# 27-AudioEncode.net
KiCad netlist of a schematic drawn in Altium Designer
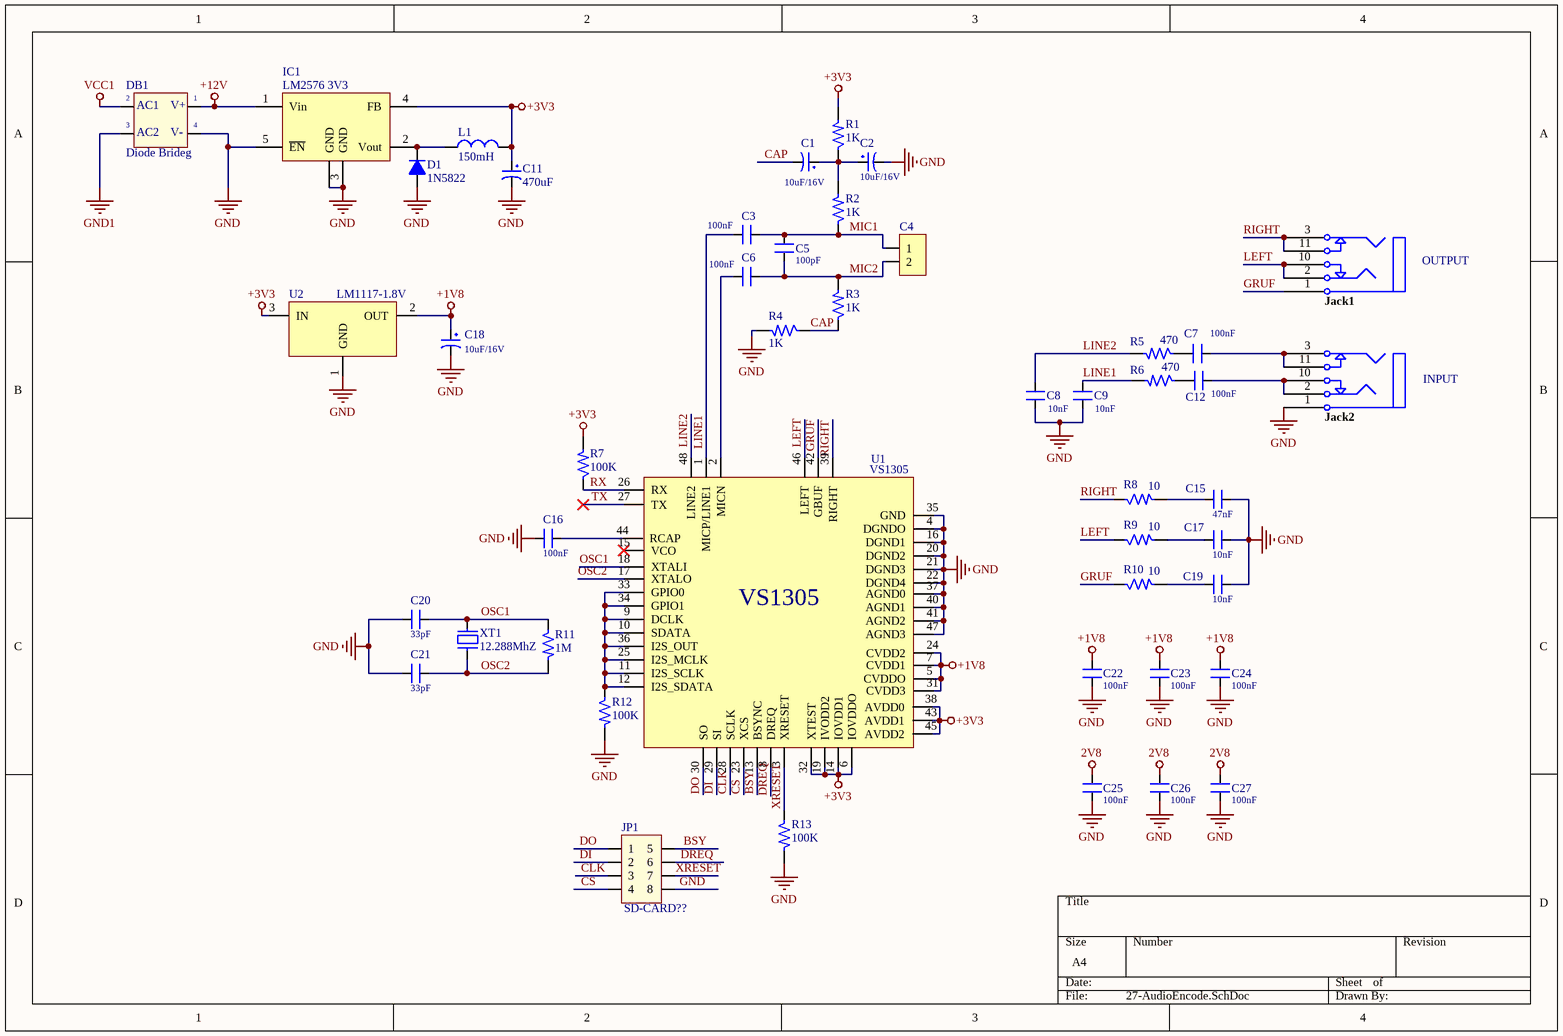
[diagram p0: 27-AudioEncode.SchDoc]

(export (version "E")
  (design (tool "Eeschema 10.0.6"))
  (components
    (comp (ref "C1") (value "10uF/16V") (footprint "C-TANT-7343") (libsource (lib "") (part "Capacitor_1")))
    (comp (ref "C2") (value "10uF/16V") (footprint "C-TANT-7343") (libsource (lib "") (part "Capacitor_1")))
    (comp (ref "C3") (value "100nF") (footprint "CER-0805") (libsource (lib "MrQuan") (part "Ceramic")))
    (comp (ref "C4")
      (value "JP2")
      (footprint "JP2-C1T")
      (description "WR-PHD 2.54 mm Angled Socket Header")
      (fields
        (field (name "MANUFACTURER") "Würth Elektronik eiSos GmbH")
        (field (name "PARTNO") "613002143121")
        (field (name "CREATED BY") "Karrer Zheng")
      )
      (libsource (lib "LIBRARY") (part "JP2"))
    )
    (comp (ref "C5") (value "100pF") (footprint "CER-0805") (libsource (lib "MrQuan") (part "Ceramic")))
    (comp (ref "C6") (value "100nF") (footprint "CER-0805") (libsource (lib "MrQuan") (part "Ceramic")))
    (comp (ref "C7") (value "100nF") (footprint "CER-0805") (libsource (lib "MrQuan") (part "Ceramic")))
    (comp (ref "C8") (value "10nF") (footprint "CER-0805") (libsource (lib "MrQuan") (part "Ceramic")))
    (comp (ref "C9") (value "10nF") (footprint "CER-0805") (libsource (lib "MrQuan") (part "Ceramic")))
    (comp (ref "C11")
      (value "470uF")
      (footprint "C-ALU-D6.5")
      (description "Cap P  0,1uF < 22uF , 16 - 50V")
      (libsource (lib "PART") (part "CP1"))
    )
    (comp (ref "C12") (value "100nF") (footprint "CER-0805") (libsource (lib "MrQuan") (part "Ceramic")))
    (comp (ref "C15") (value "47nF") (footprint "CER-0805") (libsource (lib "MrQuan") (part "Ceramic")))
    (comp (ref "C16") (value "100nF") (footprint "CER-0805") (libsource (lib "MrQuan") (part "Ceramic")))
    (comp (ref "C17") (value "10nF") (footprint "CER-0805") (libsource (lib "MrQuan") (part "Ceramic")))
    (comp (ref "C18")
      (value "10uF/16V")
      (footprint "C-TANT-7343")
      (libsource (lib "MrQuan") (part "Capacitor"))
    )
    (comp (ref "C19") (value "10nF") (footprint "CER-0805") (libsource (lib "MrQuan") (part "Ceramic")))
    (comp (ref "C20") (value "33pF") (footprint "CER-0805") (libsource (lib "MrQuan") (part "Ceramic")))
    (comp (ref "C21") (value "33pF") (footprint "CER-0805") (libsource (lib "MrQuan") (part "Ceramic")))
    (comp (ref "C22") (value "100nF") (footprint "C-0805") (libsource (lib "MrQuan") (part "Ceramic")))
    (comp (ref "C23") (value "100nF") (footprint "C-0805") (libsource (lib "MrQuan") (part "Ceramic")))
    (comp (ref "C24") (value "100nF") (footprint "C-0805") (libsource (lib "MrQuan") (part "Ceramic")))
    (comp (ref "C25") (value "100nF") (footprint "C-0805") (libsource (lib "MrQuan") (part "Ceramic")))
    (comp (ref "C26") (value "100nF") (footprint "C-0805") (libsource (lib "MrQuan") (part "Ceramic")))
    (comp (ref "C27") (value "100nF") (footprint "C-0805") (libsource (lib "MrQuan") (part "Ceramic")))
    (comp (ref "D1")
      (value "1N5822")
      (footprint "D-DO214-AB")
      (description "Diode 1A")
      (libsource (lib "PART") (part "D1A"))
    )
    (comp (ref "DB1")
      (value "Diode Brideg")
      (footprint "D-DB-1A-SMD")
      (description "Convert AC to DC voltage, 4 pin")
      (libsource (lib "PART") (part "DB"))
    )
    (comp (ref "IC1")
      (value "LM2576 3V3")
      (footprint "TO-263-5L")
      (description "LM2576")
      (libsource (lib "PART") (part "LM2576"))
    )
    (comp (ref "Jack1")
      (value "AUDIO MIC BLACK HEADER")
      (footprint "CON MIC1")
      (libsource (lib "LIBRARY") (part "CON MIC1"))
    )
    (comp (ref "Jack2")
      (value "AUDIO MIC BLACK HEADER")
      (footprint "CON MIC1")
      (libsource (lib "LIBRARY") (part "CON MIC1"))
    )
    (comp (ref "JP1")
      (value "SD-CARD??")
      (footprint "JP4x2")
      (description "Connector 4x2")
      (libsource (lib "syhaunguyen") (part "JP4x2"))
    )
    (comp (ref "L1")
      (value "150mH")
      (footprint "L-SMD-10x10")
      (description "Inductor")
      (libsource (lib "PART") (part "L1"))
    )
    (comp (ref "R1") (value "1K") (footprint "RES-0805") (libsource (lib "MrQuan") (part "Res1/4W")))
    (comp (ref "R2") (value "1K") (footprint "RES-0805") (libsource (lib "MrQuan") (part "Res1/4W")))
    (comp (ref "R3") (value "1K") (footprint "RES-0805") (libsource (lib "MrQuan") (part "Res1/4W")))
    (comp (ref "R4") (value "1K") (footprint "RES-0805") (libsource (lib "MrQuan") (part "Res1/4W")))
    (comp (ref "R5") (value "470") (footprint "RES-0805") (libsource (lib "MrQuan") (part "Res1/4W")))
    (comp (ref "R6") (value "470") (footprint "RES-0805") (libsource (lib "MrQuan") (part "Res1/4W")))
    (comp (ref "R7") (value "100K") (footprint "RES-0805") (libsource (lib "MrQuan") (part "Res1/4W")))
    (comp (ref "R8") (value "10") (footprint "RES-0805") (libsource (lib "MrQuan") (part "Res1/4W")))
    (comp (ref "R9") (value "10") (footprint "RES-0805") (libsource (lib "MrQuan") (part "Res1/4W")))
    (comp (ref "R10") (value "10") (footprint "RES-0805") (libsource (lib "MrQuan") (part "Res1/4W")))
    (comp (ref "R11") (value "1M") (footprint "RES-0805") (libsource (lib "MrQuan") (part "Res1/4W")))
    (comp (ref "R12") (value "100K") (footprint "RES-0805") (libsource (lib "MrQuan") (part "Res1/4W")))
    (comp (ref "R13") (value "100K") (footprint "RES-0805") (libsource (lib "MrQuan") (part "Res1/4W")))
    (comp (ref "U1") (value "VS1305") (footprint "QFP_48") (libsource (lib "MrQuan") (part "VS1305")))
    (comp (ref "U2")
      (value "LM1117-1.8V")
      (footprint "SOT223")
      (description "800mA Low-Dropout Linear Regulator")
      (fields (field (name "CREATOR") "Nguyen Ba Bien"))
      (libsource (lib "LIBRARY") (part "LM1117"))
    )
    (comp (ref "XT1") (value "12.288MhZ") (footprint "XT SMD5032") (libsource (lib "MrQuan") (part "XT")))
  )
  (nets
    (net (code "1") (name "+1V8") (class "Default")
      (node (ref "C18") (pin "1") (pinfunction "1_1") (pintype "passive"))
      (node (ref "C22") (pin "2") (pinfunction "2_2") (pintype "passive"))
      (node (ref "C23") (pin "2") (pinfunction "2_2") (pintype "passive"))
      (node (ref "C24") (pin "2") (pinfunction "2_2") (pintype "passive"))
      (node (ref "U2") (pin "2") (pinfunction "OUT_2") (pintype "passive"))
    )
    (net (code "2") (name "+3V3") (class "Default")
      (node (ref "C11") (pin "1") (pinfunction "1_1") (pintype "passive"))
      (node (ref "IC1") (pin "4") (pinfunction "FB_4") (pintype "passive"))
      (node (ref "L1") (pin "2") (pinfunction "2_2") (pintype "passive"))
      (node (ref "R1") (pin "2") (pinfunction "2_2") (pintype "passive"))
      (node (ref "R7") (pin "2") (pinfunction "2_2") (pintype "passive"))
      (node (ref "U1") (pin "14") (pinfunction "IOVDD1_14") (pintype "passive"))
      (node (ref "U1") (pin "19") (pinfunction "IVODD2_19") (pintype "passive"))
      (node (ref "U1") (pin "32") (pinfunction "XTEST_32") (pintype "passive"))
      (node (ref "U1") (pin "6") (pinfunction "IOVDDO_6") (pintype "passive"))
      (node (ref "U2") (pin "3") (pinfunction "IN_3") (pintype "passive"))
    )
    (net (code "3") (name "+12V") (class "Default")
      (node (ref "DB1") (pin "3") (pinfunction "AC2_3") (pintype "passive"))
      (node (ref "IC1") (pin "1") (pinfunction "Vin_1") (pintype "passive"))
    )
    (net (code "4") (name "/BSY") (class "Default")
      (node (ref "JP1") (pin "5") (pinfunction "5_5") (pintype "passive"))
      (node (ref "U1") (pin "13") (pinfunction "BSYNC_13") (pintype "passive"))
    )
    (net (code "5") (name "/CAP") (class "Default")
      (node (ref "C1") (pin "2") (pinfunction "2_2") (pintype "passive"))
      (node (ref "R3") (pin "1") (pinfunction "1_1") (pintype "passive"))
      (node (ref "R4") (pin "1") (pinfunction "1_1") (pintype "passive"))
    )
    (net (code "6") (name "/CLK") (class "Default")
      (node (ref "JP1") (pin "3") (pinfunction "3_3") (pintype "passive"))
      (node (ref "U1") (pin "28") (pinfunction "SCLK_28") (pintype "passive"))
    )
    (net (code "7") (name "/CS") (class "Default")
      (node (ref "JP1") (pin "4") (pinfunction "4_4") (pintype "passive"))
      (node (ref "U1") (pin "23") (pinfunction "XCS_23") (pintype "passive"))
    )
    (net (code "8") (name "/DI") (class "Default")
      (node (ref "JP1") (pin "2") (pinfunction "2_2") (pintype "passive"))
      (node (ref "U1") (pin "29") (pinfunction "SI_29") (pintype "passive"))
    )
    (net (code "9") (name "/DO") (class "Default")
      (node (ref "JP1") (pin "1") (pinfunction "1_1") (pintype "passive"))
      (node (ref "U1") (pin "30") (pinfunction "SO_30") (pintype "passive"))
    )
    (net (code "10") (name "/DREQ") (class "Default")
      (node (ref "JP1") (pin "6") (pinfunction "6_6") (pintype "passive"))
      (node (ref "U1") (pin "8") (pinfunction "DREQ_8") (pintype "passive"))
    )
    (net (code "11") (name "/GRUF") (class "Default")
      (node (ref "Jack1") (pin "1") (pintype "passive"))
      (node (ref "R10") (pin "1") (pinfunction "1_1") (pintype "passive"))
      (node (ref "U1") (pin "42") (pinfunction "GBUF_42") (pintype "passive"))
    )
    (net (code "12") (name "/LEFT") (class "Default")
      (node (ref "Jack1") (pin "10") (pintype "passive"))
      (node (ref "Jack1") (pin "2") (pintype "passive"))
      (node (ref "R9") (pin "1") (pinfunction "1_1") (pintype "passive"))
      (node (ref "U1") (pin "46") (pinfunction "LEFT_46") (pintype "passive"))
    )
    (net (code "13") (name "/LINE1") (class "Default")
      (node (ref "C3") (pin "2") (pinfunction "2_2") (pintype "passive"))
      (node (ref "C9") (pin "2") (pinfunction "2_2") (pintype "passive"))
      (node (ref "R6") (pin "2") (pinfunction "2_2") (pintype "passive"))
      (node (ref "U1") (pin "1") (pinfunction "MICP/LINE1_1") (pintype "passive"))
    )
    (net (code "14") (name "/LINE2") (class "Default")
      (node (ref "C8") (pin "2") (pinfunction "2_2") (pintype "passive"))
      (node (ref "R5") (pin "2") (pinfunction "2_2") (pintype "passive"))
      (node (ref "U1") (pin "48") (pinfunction "LINE2_48") (pintype "passive"))
    )
    (net (code "15") (name "/MIC1") (class "Default")
      (node (ref "C3") (pin "1") (pinfunction "1_1") (pintype "passive"))
      (node (ref "C4") (pin "1") (pinfunction "1_1") (pintype "passive"))
      (node (ref "C5") (pin "1") (pinfunction "1_1") (pintype "passive"))
      (node (ref "R2") (pin "1") (pinfunction "1_1") (pintype "passive"))
    )
    (net (code "16") (name "/MIC2") (class "Default")
      (node (ref "C4") (pin "2") (pinfunction "2_2") (pintype "passive"))
      (node (ref "C5") (pin "2") (pinfunction "2_2") (pintype "passive"))
      (node (ref "C6") (pin "1") (pinfunction "1_1") (pintype "passive"))
      (node (ref "R3") (pin "2") (pinfunction "2_2") (pintype "passive"))
    )
    (net (code "17") (name "/OSC1") (class "Default")
      (node (ref "C20") (pin "2") (pinfunction "2_2") (pintype "passive"))
      (node (ref "R11") (pin "1") (pinfunction "1_1") (pintype "passive"))
      (node (ref "U1") (pin "18") (pinfunction "XTALI_18") (pintype "passive"))
      (node (ref "XT1") (pin "2") (pinfunction "2_2") (pintype "passive"))
    )
    (net (code "18") (name "/OSC2") (class "Default")
      (node (ref "C21") (pin "2") (pinfunction "2_2") (pintype "passive"))
      (node (ref "R11") (pin "2") (pinfunction "2_2") (pintype "passive"))
      (node (ref "U1") (pin "17") (pinfunction "XTALO_17") (pintype "passive"))
      (node (ref "XT1") (pin "1") (pinfunction "1_1") (pintype "passive"))
    )
    (net (code "19") (name "/RIGHT") (class "Default")
      (node (ref "Jack1") (pin "11") (pintype "passive"))
      (node (ref "Jack1") (pin "3") (pintype "passive"))
      (node (ref "R8") (pin "1") (pinfunction "1_1") (pintype "passive"))
      (node (ref "U1") (pin "39") (pinfunction "RIGHT_39") (pintype "passive"))
    )
    (net (code "20") (name "/RX") (class "Default")
      (node (ref "R7") (pin "1") (pinfunction "1_1") (pintype "passive"))
      (node (ref "U1") (pin "26") (pinfunction "RX_26") (pintype "passive"))
    )
    (net (code "21") (name "/TX") (class "Default")
      (node (ref "U1") (pin "27") (pinfunction "TX_27") (pintype "passive+no_connect"))
    )
    (net (code "22") (name "/XRESET") (class "Default")
      (node (ref "JP1") (pin "7") (pinfunction "7_7") (pintype "passive"))
      (node (ref "R13") (pin "1") (pinfunction "1_1") (pintype "passive"))
      (node (ref "U1") (pin "3") (pinfunction "XRESET_3") (pintype "passive"))
    )
    (net (code "23") (name "2V8") (class "Default")
      (node (ref "C25") (pin "2") (pinfunction "2_2") (pintype "passive"))
      (node (ref "C26") (pin "2") (pinfunction "2_2") (pintype "passive"))
      (node (ref "C27") (pin "2") (pinfunction "2_2") (pintype "passive"))
    )
    (net (code "24") (name "GND") (class "Default")
      (node (ref "C11") (pin "2") (pinfunction "2_2") (pintype "passive"))
      (node (ref "C15") (pin "2") (pinfunction "2_2") (pintype "passive"))
      (node (ref "C16") (pin "1") (pinfunction "1_1") (pintype "passive"))
      (node (ref "C17") (pin "2") (pinfunction "2_2") (pintype "passive"))
      (node (ref "C18") (pin "2") (pinfunction "2_2") (pintype "passive"))
      (node (ref "C19") (pin "2") (pinfunction "2_2") (pintype "passive"))
      (node (ref "C2") (pin "2") (pinfunction "2_2") (pintype "passive"))
      (node (ref "C20") (pin "1") (pinfunction "1_1") (pintype "passive"))
      (node (ref "C21") (pin "1") (pinfunction "1_1") (pintype "passive"))
      (node (ref "C22") (pin "1") (pinfunction "1_1") (pintype "passive"))
      (node (ref "C23") (pin "1") (pinfunction "1_1") (pintype "passive"))
      (node (ref "C24") (pin "1") (pinfunction "1_1") (pintype "passive"))
      (node (ref "C25") (pin "1") (pinfunction "1_1") (pintype "passive"))
      (node (ref "C26") (pin "1") (pinfunction "1_1") (pintype "passive"))
      (node (ref "C27") (pin "1") (pinfunction "1_1") (pintype "passive"))
      (node (ref "C8") (pin "1") (pinfunction "1_1") (pintype "passive"))
      (node (ref "C9") (pin "1") (pinfunction "1_1") (pintype "passive"))
      (node (ref "D1") (pin "1") (pinfunction "A_1") (pintype "passive"))
      (node (ref "DB1") (pin "4") (pinfunction "-V_OUT_4") (pintype "passive"))
      (node (ref "IC1") (pin "3") (pinfunction "GND_3") (pintype "passive"))
      (node (ref "IC1") (pin "5") (pinfunction "~{EN}_5") (pintype "passive"))
      (node (ref "IC1") (pin "HM") (pinfunction "GND_HM") (pintype "passive"))
      (node (ref "JP1") (pin "8") (pinfunction "8_8") (pintype "passive"))
      (node (ref "Jack2") (pin "1") (pintype "passive"))
      (node (ref "R12") (pin "2") (pinfunction "2_2") (pintype "passive"))
      (node (ref "R13") (pin "2") (pinfunction "2_2") (pintype "passive"))
      (node (ref "R4") (pin "2") (pinfunction "2_2") (pintype "passive"))
      (node (ref "U1") (pin "16") (pinfunction "DGND1_16") (pintype "passive"))
      (node (ref "U1") (pin "20") (pinfunction "DGND2_20") (pintype "passive"))
      (node (ref "U1") (pin "21") (pinfunction "DGND3_21") (pintype "passive"))
      (node (ref "U1") (pin "22") (pinfunction "DGND4_22") (pintype "passive"))
      (node (ref "U1") (pin "35") (pinfunction "GND_35") (pintype "passive"))
      (node (ref "U1") (pin "37") (pinfunction "AGND0_37") (pintype "passive"))
      (node (ref "U1") (pin "4") (pinfunction "DGNDO_4") (pintype "passive"))
      (node (ref "U1") (pin "40") (pinfunction "AGND1_40") (pintype "passive"))
      (node (ref "U1") (pin "41") (pinfunction "AGND2_41") (pintype "passive"))
      (node (ref "U1") (pin "47") (pinfunction "AGND3_47") (pintype "passive"))
      (node (ref "U2") (pin "1") (pinfunction "GND_1") (pintype "passive"))
    )
    (net (code "25") (name "GND1") (class "Default")
      (node (ref "DB1") (pin "1") (pinfunction "+V_OUT_1") (pintype "passive"))
    )
    (net (code "26") (name "Net-(C1-Pad1)") (class "Default")
      (node (ref "C1") (pin "1") (pinfunction "1_1") (pintype "passive"))
      (node (ref "C2") (pin "1") (pinfunction "1_1") (pintype "passive"))
      (node (ref "R1") (pin "1") (pinfunction "1_1") (pintype "passive"))
      (node (ref "R2") (pin "2") (pinfunction "2_2") (pintype "passive"))
    )
    (net (code "27") (name "Net-(C7-Pad1)") (class "Default")
      (node (ref "C7") (pin "1") (pinfunction "1_1") (pintype "passive"))
      (node (ref "R5") (pin "1") (pinfunction "1_1") (pintype "passive"))
    )
    (net (code "28") (name "Net-(C7-Pad2)") (class "Default")
      (node (ref "C7") (pin "2") (pinfunction "2_2") (pintype "passive"))
      (node (ref "Jack2") (pin "11") (pintype "passive"))
      (node (ref "Jack2") (pin "3") (pintype "passive"))
    )
    (net (code "29") (name "Net-(C12-Pad1)") (class "Default")
      (node (ref "C12") (pin "1") (pinfunction "1_1") (pintype "passive"))
      (node (ref "R6") (pin "1") (pinfunction "1_1") (pintype "passive"))
    )
    (net (code "30") (name "Net-(C12-Pad2)") (class "Default")
      (node (ref "C12") (pin "2") (pinfunction "2_2") (pintype "passive"))
      (node (ref "Jack2") (pin "10") (pintype "passive"))
      (node (ref "Jack2") (pin "2") (pintype "passive"))
    )
    (net (code "31") (name "Net-(C15-Pad1)") (class "Default")
      (node (ref "C15") (pin "1") (pinfunction "1_1") (pintype "passive"))
      (node (ref "R8") (pin "2") (pinfunction "2_2") (pintype "passive"))
    )
    (net (code "32") (name "Net-(C17-Pad1)") (class "Default")
      (node (ref "C17") (pin "1") (pinfunction "1_1") (pintype "passive"))
      (node (ref "R9") (pin "2") (pinfunction "2_2") (pintype "passive"))
    )
    (net (code "33") (name "Net-(C19-Pad1)") (class "Default")
      (node (ref "C19") (pin "1") (pinfunction "1_1") (pintype "passive"))
      (node (ref "R10") (pin "2") (pinfunction "2_2") (pintype "passive"))
    )
    (net (code "34") (name "Net-(D1-K)") (class "Default")
      (node (ref "D1") (pin "2") (pinfunction "K_2") (pintype "passive"))
      (node (ref "IC1") (pin "2") (pinfunction "Vout_2") (pintype "passive"))
      (node (ref "L1") (pin "1") (pinfunction "1_1") (pintype "passive"))
    )
    (net (code "35") (name "Net-(U1-AVDD0)") (class "Default")
      (node (ref "U1") (pin "38") (pinfunction "AVDD0_38") (pintype "passive"))
      (node (ref "U1") (pin "43") (pinfunction "AVDD1_43") (pintype "passive"))
      (node (ref "U1") (pin "45") (pinfunction "AVDD2_45") (pintype "passive"))
    )
    (net (code "36") (name "Net-(U1-CVDD1)") (class "Default")
      (node (ref "U1") (pin "24") (pinfunction "CVDD2_24") (pintype "passive"))
      (node (ref "U1") (pin "31") (pinfunction "CVDD3_31") (pintype "passive"))
      (node (ref "U1") (pin "5") (pinfunction "CVDDO_5") (pintype "passive"))
      (node (ref "U1") (pin "7") (pinfunction "CVDD1_7") (pintype "passive"))
    )
    (net (code "37") (name "Net-(U1-DCLK)") (class "Default")
      (node (ref "R12") (pin "1") (pinfunction "1_1") (pintype "passive"))
      (node (ref "U1") (pin "10") (pinfunction "SDATA_10") (pintype "passive"))
      (node (ref "U1") (pin "11") (pinfunction "I2S_SCLK_11") (pintype "passive"))
      (node (ref "U1") (pin "12") (pinfunction "I2S_SDATA_12") (pintype "passive"))
      (node (ref "U1") (pin "25") (pinfunction "I2S_MCLK_25") (pintype "passive"))
      (node (ref "U1") (pin "33") (pinfunction "GPIO0_33") (pintype "passive"))
      (node (ref "U1") (pin "34") (pinfunction "GPIO1_34") (pintype "passive"))
      (node (ref "U1") (pin "36") (pinfunction "I2S_OUT_36") (pintype "passive"))
      (node (ref "U1") (pin "9") (pinfunction "DCLK_9") (pintype "passive"))
    )
    (net (code "38") (name "Net-(U1-MICN)") (class "Default")
      (node (ref "C6") (pin "2") (pinfunction "2_2") (pintype "passive"))
      (node (ref "U1") (pin "2") (pinfunction "MICN_2") (pintype "passive"))
    )
    (net (code "39") (name "Net-(U1-RCAP)") (class "Default")
      (node (ref "C16") (pin "2") (pinfunction "2_2") (pintype "passive"))
      (node (ref "U1") (pin "44") (pinfunction "RCAP_44") (pintype "passive"))
    )
    (net (code "40") (name "VCC1") (class "Default")
      (node (ref "DB1") (pin "2") (pinfunction "AC1_2") (pintype "passive"))
    )
    (net (code "41") (name "unconnected-(U1-VCO-Pad15)") (class "Default")
      (node (ref "U1") (pin "15") (pinfunction "VCO_15") (pintype "passive+no_connect"))
    )
  )
)
